# sgnd_rings.net
KiCad netlist of a schematic drawn in Altium Designer
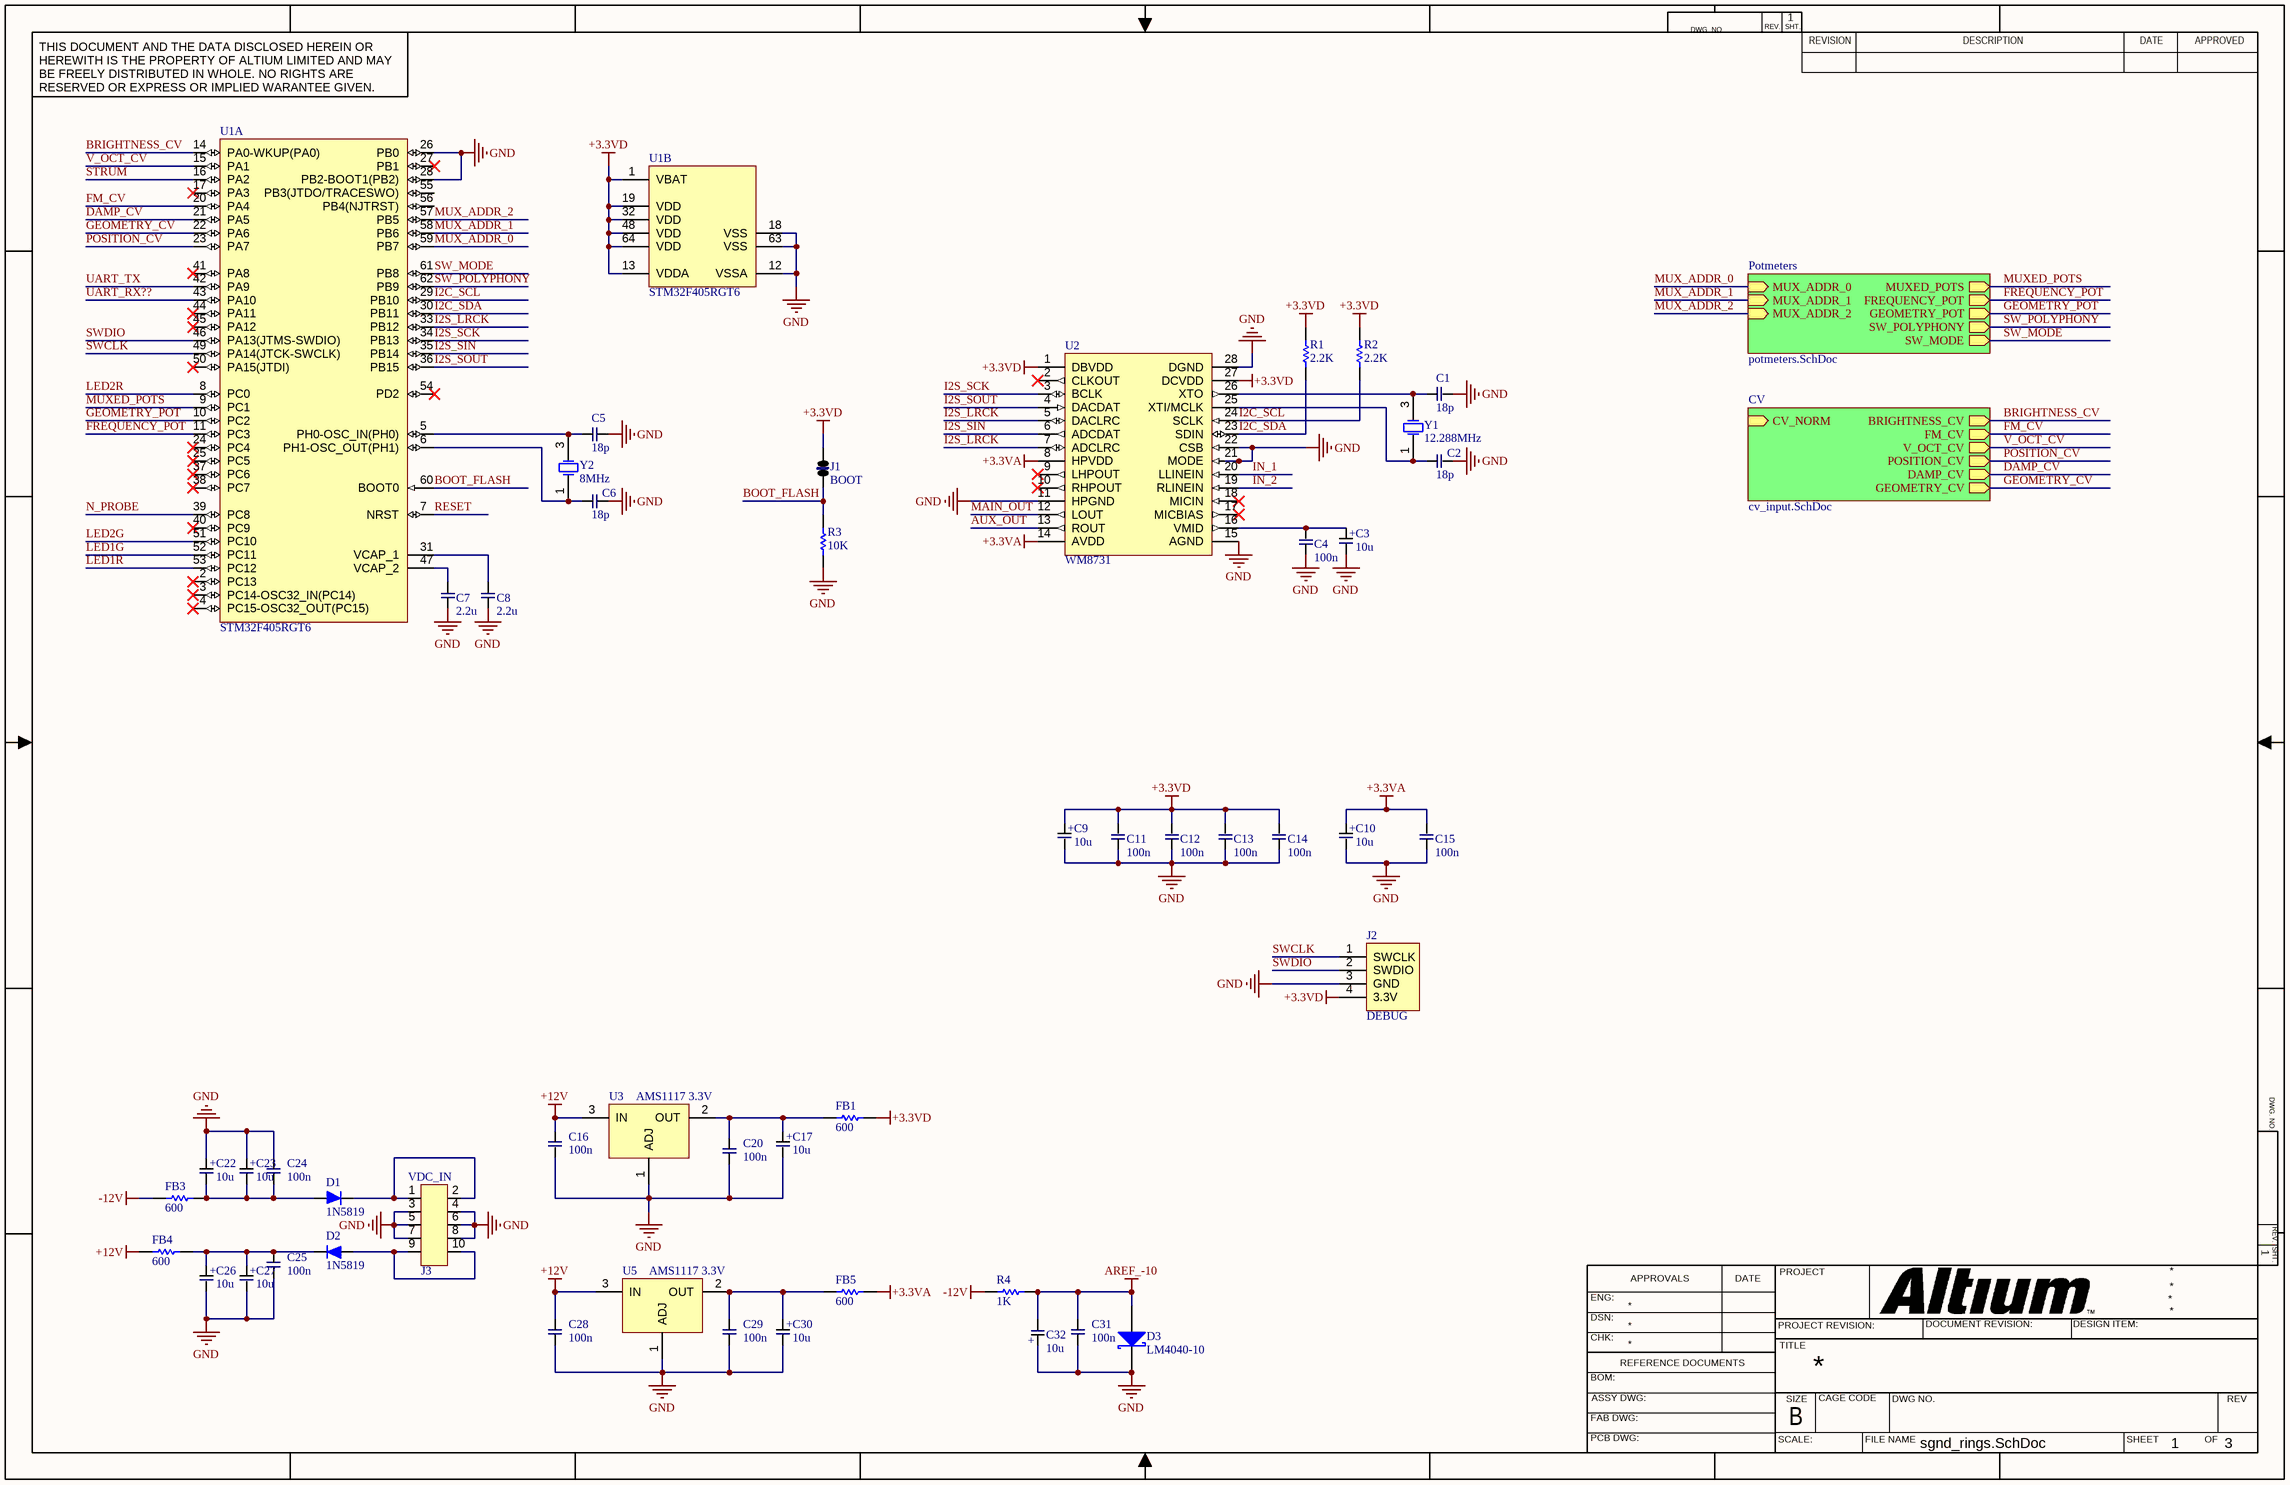
[diagram p0: sgnd_rings.SchDoc]

(export (version "E")
  (design (tool "Eeschema 10.0.6"))
  (components
    (comp (ref "C1")
      (value "18p")
      (footprint "C0603")
      (description "Capacitor (Semiconductor SIM Model)")
      (fields (field (name "Comment") "Capacitor") (field (name "PUBLISHER") "Altium Limited"))
      (libsource (lib "ryzerd") (part "Capacitor"))
    )
    (comp (ref "C2")
      (value "18p")
      (footprint "C0603")
      (description "Capacitor (Semiconductor SIM Model)")
      (fields (field (name "Comment") "Capacitor") (field (name "PUBLISHER") "Altium Limited"))
      (libsource (lib "ryzerd") (part "Capacitor"))
    )
    (comp (ref "C3")
      (value "10u")
      (footprint "ELCO_SMD_4x5.3mm")
      (fields (field (name "Comment") "C_ELCO"))
      (libsource (lib "ryzerd") (part "C_ELCO"))
    )
    (comp (ref "C4")
      (value "100n")
      (footprint "C0603")
      (description "Capacitor (Semiconductor SIM Model)")
      (fields (field (name "Comment") "Capacitor") (field (name "PUBLISHER") "Altium Limited"))
      (libsource (lib "ryzerd") (part "Capacitor"))
    )
    (comp (ref "C5")
      (value "18p")
      (footprint "C0603")
      (description "Capacitor (Semiconductor SIM Model)")
      (fields (field (name "Comment") "Capacitor") (field (name "PUBLISHER") "Altium Limited"))
      (libsource (lib "ryzerd") (part "Capacitor"))
    )
    (comp (ref "C6")
      (value "18p")
      (footprint "C0603")
      (description "Capacitor (Semiconductor SIM Model)")
      (fields (field (name "Comment") "Capacitor") (field (name "PUBLISHER") "Altium Limited"))
      (libsource (lib "ryzerd") (part "Capacitor"))
    )
    (comp (ref "C7")
      (value "2.2u")
      (footprint "C0603")
      (description "Capacitor (Semiconductor SIM Model)")
      (fields (field (name "Comment") "Capacitor") (field (name "PUBLISHER") "Altium Limited"))
      (libsource (lib "ryzerd") (part "Capacitor"))
    )
    (comp (ref "C8")
      (value "2.2u")
      (footprint "C0603")
      (description "Capacitor (Semiconductor SIM Model)")
      (fields (field (name "Comment") "Capacitor") (field (name "PUBLISHER") "Altium Limited"))
      (libsource (lib "ryzerd") (part "Capacitor"))
    )
    (comp (ref "C9")
      (value "10u")
      (footprint "ELCO_SMD_4x5.3mm")
      (fields (field (name "Comment") "C_ELCO"))
      (libsource (lib "ryzerd") (part "C_ELCO"))
    )
    (comp (ref "C10")
      (value "10u")
      (footprint "ELCO_SMD_4x5.3mm")
      (fields (field (name "Comment") "C_ELCO"))
      (libsource (lib "ryzerd") (part "C_ELCO"))
    )
    (comp (ref "C11")
      (value "100n")
      (footprint "C0603")
      (description "Capacitor (Semiconductor SIM Model)")
      (fields (field (name "Comment") "Capacitor") (field (name "PUBLISHER") "Altium Limited"))
      (libsource (lib "ryzerd") (part "Capacitor"))
    )
    (comp (ref "C12")
      (value "100n")
      (footprint "C0603")
      (description "Capacitor (Semiconductor SIM Model)")
      (fields (field (name "Comment") "Capacitor") (field (name "PUBLISHER") "Altium Limited"))
      (libsource (lib "ryzerd") (part "Capacitor"))
    )
    (comp (ref "C13")
      (value "100n")
      (footprint "C0603")
      (description "Capacitor (Semiconductor SIM Model)")
      (fields (field (name "Comment") "Capacitor") (field (name "PUBLISHER") "Altium Limited"))
      (libsource (lib "ryzerd") (part "Capacitor"))
    )
    (comp (ref "C14")
      (value "100n")
      (footprint "C0603")
      (description "Capacitor (Semiconductor SIM Model)")
      (fields (field (name "Comment") "Capacitor") (field (name "PUBLISHER") "Altium Limited"))
      (libsource (lib "ryzerd") (part "Capacitor"))
    )
    (comp (ref "C15")
      (value "100n")
      (footprint "C0603")
      (description "Capacitor (Semiconductor SIM Model)")
      (fields (field (name "Comment") "Capacitor") (field (name "PUBLISHER") "Altium Limited"))
      (libsource (lib "ryzerd") (part "Capacitor"))
    )
    (comp (ref "C16")
      (value "100n")
      (footprint "C0603")
      (description "Capacitor (Semiconductor SIM Model)")
      (fields (field (name "Comment") "Capacitor") (field (name "PUBLISHER") "Altium Limited"))
      (libsource (lib "ryzerd") (part "Capacitor"))
    )
    (comp (ref "C17")
      (value "10u")
      (footprint "ELCO_SMD_4x5.3mm")
      (fields (field (name "Comment") "C_ELCO"))
      (libsource (lib "ryzerd") (part "C_ELCO"))
    )
    (comp (ref "C20")
      (value "100n")
      (footprint "C0603")
      (description "Capacitor (Semiconductor SIM Model)")
      (fields (field (name "Comment") "Capacitor") (field (name "PUBLISHER") "Altium Limited"))
      (libsource (lib "ryzerd") (part "Capacitor"))
    )
    (comp (ref "C22")
      (value "10u")
      (footprint "ELCO_SMD_4x5.3mm")
      (fields (field (name "Comment") "C_ELCO"))
      (libsource (lib "ryzerd") (part "C_ELCO"))
    )
    (comp (ref "C23")
      (value "10u")
      (footprint "ELCO_SMD_4x5.3mm")
      (fields (field (name "Comment") "C_ELCO"))
      (libsource (lib "ryzerd") (part "C_ELCO"))
    )
    (comp (ref "C24")
      (value "100n")
      (footprint "C0603")
      (description "Capacitor (Semiconductor SIM Model)")
      (fields (field (name "Comment") "Capacitor") (field (name "PUBLISHER") "Altium Limited"))
      (libsource (lib "ryzerd") (part "Capacitor"))
    )
    (comp (ref "C25")
      (value "100n")
      (footprint "C0603")
      (description "Capacitor (Semiconductor SIM Model)")
      (fields (field (name "Comment") "Capacitor") (field (name "PUBLISHER") "Altium Limited"))
      (libsource (lib "ryzerd") (part "Capacitor"))
    )
    (comp (ref "C26")
      (value "10u")
      (footprint "ELCO_SMD_4x5.3mm")
      (fields (field (name "Comment") "C_ELCO"))
      (libsource (lib "ryzerd") (part "C_ELCO"))
    )
    (comp (ref "C27")
      (value "10u")
      (footprint "ELCO_SMD_4x5.3mm")
      (fields (field (name "Comment") "C_ELCO"))
      (libsource (lib "ryzerd") (part "C_ELCO"))
    )
    (comp (ref "C28")
      (value "100n")
      (footprint "C0603")
      (description "Capacitor (Semiconductor SIM Model)")
      (fields (field (name "Comment") "Capacitor") (field (name "PUBLISHER") "Altium Limited"))
      (libsource (lib "ryzerd") (part "Capacitor"))
    )
    (comp (ref "C29")
      (value "100n")
      (footprint "C0603")
      (description "Capacitor (Semiconductor SIM Model)")
      (fields (field (name "Comment") "Capacitor") (field (name "PUBLISHER") "Altium Limited"))
      (libsource (lib "ryzerd") (part "Capacitor"))
    )
    (comp (ref "C30")
      (value "10u")
      (footprint "ELCO_SMD_4x5.3mm")
      (fields (field (name "Comment") "C_ELCO"))
      (libsource (lib "ryzerd") (part "C_ELCO"))
    )
    (comp (ref "C31")
      (value "100n")
      (footprint "C0603")
      (description "Capacitor (Semiconductor SIM Model)")
      (fields (field (name "Comment") "Capacitor") (field (name "PUBLISHER") "Altium Limited"))
      (libsource (lib "ryzerd") (part "Capacitor"))
    )
    (comp (ref "C32")
      (value "10u")
      (footprint "ELCO_SMD_4x5.3mm")
      (fields (field (name "Comment") "C_ELCO"))
      (libsource (lib "ryzerd") (part "C_ELCO"))
    )
    (comp (ref "D1")
      (value "1N5819")
      (footprint "DIODE_SOD-123")
      (description "1 Amp General Purpose Rectifier")
      (fields (field (name "Comment") "1N4148") (field (name "PUBLISHER") "Altium Limited"))
      (libsource (lib "ryzerd") (part "1N5819"))
    )
    (comp (ref "D2")
      (value "1N5819")
      (footprint "DIODE_SOD-123")
      (description "1 Amp General Purpose Rectifier")
      (fields (field (name "Comment") "1N4148") (field (name "PUBLISHER") "Altium Limited"))
      (libsource (lib "ryzerd") (part "1N5819"))
    )
    (comp (ref "D3")
      (value "LM4040-10")
      (footprint "SOT-23_M")
      (description "LM4040 Precision Micropower Shunt Voltage Reference 10V")
      (fields (field (name "JLC PART NUMBER") "C201738"))
      (libsource (lib "ryzerd") (part "LM4040-10"))
    )
    (comp (ref "FB1")
      (value "600")
      (footprint "R0603")
      (description "Resistor")
      (fields (field (name "Comment") "RESISTOR") (field (name "PUBLISHER") "Altium Limited"))
      (libsource (lib "ryzerd") (part "RESISTOR"))
    )
    (comp (ref "FB3")
      (value "600")
      (footprint "R0603")
      (description "Resistor")
      (fields (field (name "Comment") "RESISTOR") (field (name "PUBLISHER") "Altium Limited"))
      (libsource (lib "ryzerd") (part "RESISTOR"))
    )
    (comp (ref "FB4")
      (value "600")
      (footprint "R0603")
      (description "Resistor")
      (fields (field (name "Comment") "RESISTOR") (field (name "PUBLISHER") "Altium Limited"))
      (libsource (lib "ryzerd") (part "RESISTOR"))
    )
    (comp (ref "FB5")
      (value "600")
      (footprint "R0603")
      (description "Resistor")
      (fields (field (name "Comment") "RESISTOR") (field (name "PUBLISHER") "Altium Limited"))
      (libsource (lib "ryzerd") (part "RESISTOR"))
    )
    (comp (ref "J1")
      (value "BOOT")
      (footprint "JUMPER_2.54")
      (description "Jumper Wire")
      (fields (field (name "PUBLISHER") "Altium Limited"))
      (libsource (lib "ryzerd") (part "Jumper"))
    )
    (comp (ref "J2")
      (value "DEBUG")
      (footprint "4PIN_CONNECTOR_VERTICAL_1,25MM_P - duplicate")
      (libsource (lib "ryzerd") (part "STM32_SWD_PROGRAMMER"))
    )
    (comp (ref "J3")
      (value "IDC_socket_10pin")
      (footprint "IDC10")
      (libsource (lib "part_library_by.Craft") (part "IDC_socket_10pin"))
    )
    (comp (ref "R1")
      (value "2.2K")
      (footprint "R0603")
      (description "Resistor")
      (fields (field (name "Comment") "RESISTOR") (field (name "PUBLISHER") "Altium Limited"))
      (libsource (lib "ryzerd") (part "RESISTOR"))
    )
    (comp (ref "R2")
      (value "2.2K")
      (footprint "R0603")
      (description "Resistor")
      (fields (field (name "Comment") "RESISTOR") (field (name "PUBLISHER") "Altium Limited"))
      (libsource (lib "ryzerd") (part "RESISTOR"))
    )
    (comp (ref "R3")
      (value "10K")
      (footprint "R0603")
      (description "Resistor")
      (fields (field (name "Comment") "RESISTOR") (field (name "PUBLISHER") "Altium Limited"))
      (libsource (lib "ryzerd") (part "RESISTOR"))
    )
    (comp (ref "R4")
      (value "1K")
      (footprint "R0603")
      (description "Resistor")
      (fields (field (name "Comment") "RESISTOR") (field (name "PUBLISHER") "Altium Limited"))
      (libsource (lib "ryzerd") (part "RESISTOR"))
    )
    (comp (ref "U1")
      (value "STM32F405RGT6")
      (footprint "STM-LQFP64_N")
      (fields (field (name "MANUFACTURER") "STMicroelectronics"))
      (libsource (lib "ryzerd") (part "STM32F405RGT6"))
    )
    (comp (ref "U2")
      (value "WM8731")
      (footprint "SSOP-28_L")
      (description "Portable Internet Audio CODEC with Headphone Driver\r\nand Programmable Sample Rates")
      (fields (field (name "MANUFACTURER") "Microchip") (field (name "PARTNUMBER") "MCP4822-E/P"))
      (libsource (lib "ryzerd") (part "WM8731"))
    )
    (comp (ref "U3")
      (value "AMS1117 3.3V")
      (footprint "SOT223")
      (fields (field (name "Comment") "AMS1117_5V"))
      (libsource (lib "ryzerd") (part "AMS1117_5V"))
    )
    (comp (ref "U5")
      (value "AMS1117 3.3V")
      (footprint "SOT223")
      (fields (field (name "Comment") "AMS1117_5V"))
      (libsource (lib "ryzerd") (part "AMS1117_5V"))
    )
    (comp (ref "Y1")
      (value "12.288MHz")
      (footprint "XTAL_SMD_3.2x2.5x0.8")
      (description "Crystal Oscillator")
      (fields (field (name "PUBLISHER") "Altium Limited"))
      (libsource (lib "ryzerd") (part "XTAL_3225-24.576M-SR"))
    )
    (comp (ref "Y2")
      (value "8MHz")
      (footprint "XTAL_SMD_3.2x2.5x0.8")
      (description "Crystal Oscillator")
      (fields (field (name "PUBLISHER") "Altium Limited"))
      (libsource (lib "ryzerd") (part "XTAL_3225-24.576M-SR"))
    )
  )
  (nets
    (net (code "1") (name "+3.3VA") (class "Default")
      (node (ref "C10") (pin "1") (pinfunction "+_1") (pintype "passive"))
      (node (ref "C15") (pin "2") (pinfunction "2_2") (pintype "passive"))
      (node (ref "FB5") (pin "1") (pinfunction "1_1") (pintype "passive"))
      (node (ref "U2") (pin "14") (pinfunction "AVDD_14") (pintype "power_in"))
      (node (ref "U2") (pin "8") (pinfunction "HPVDD_8") (pintype "power_in"))
    )
    (net (code "2") (name "+3.3VD") (class "Default")
      (node (ref "C11") (pin "2") (pinfunction "2_2") (pintype "passive"))
      (node (ref "C12") (pin "2") (pinfunction "2_2") (pintype "passive"))
      (node (ref "C13") (pin "2") (pinfunction "2_2") (pintype "passive"))
      (node (ref "C14") (pin "2") (pinfunction "2_2") (pintype "passive"))
      (node (ref "C9") (pin "1") (pinfunction "+_1") (pintype "passive"))
      (node (ref "FB1") (pin "1") (pinfunction "1_1") (pintype "passive"))
      (node (ref "J1") (pin "2") (pinfunction "C2_2") (pintype "passive"))
      (node (ref "J2") (pin "4") (pinfunction "3.3V_4") (pintype "passive"))
      (node (ref "R1") (pin "2") (pinfunction "2_2") (pintype "passive"))
      (node (ref "R2") (pin "2") (pinfunction "2_2") (pintype "passive"))
      (node (ref "U1") (pin "1") (pinfunction "VBAT_1") (pintype "power_in"))
      (node (ref "U1") (pin "13") (pinfunction "VDDA_13") (pintype "power_in"))
      (node (ref "U1") (pin "19") (pinfunction "VDD_19") (pintype "power_in"))
      (node (ref "U1") (pin "32") (pinfunction "VDD_32") (pintype "power_in"))
      (node (ref "U1") (pin "48") (pinfunction "VDD_48") (pintype "power_in"))
      (node (ref "U1") (pin "64") (pinfunction "VDD_64") (pintype "power_in"))
      (node (ref "U2") (pin "1") (pinfunction "DBVDD_1") (pintype "power_in"))
      (node (ref "U2") (pin "27") (pinfunction "DCVDD_27") (pintype "power_in"))
    )
    (net (code "3") (name "+12V") (class "Default")
      (node (ref "C16") (pin "1") (pinfunction "1_1") (pintype "passive"))
      (node (ref "C28") (pin "1") (pinfunction "1_1") (pintype "passive"))
      (node (ref "FB4") (pin "2") (pinfunction "2_2") (pintype "passive"))
      (node (ref "U3") (pin "3") (pinfunction "IN_3") (pintype "passive"))
      (node (ref "U5") (pin "3") (pinfunction "IN_3") (pintype "passive"))
    )
    (net (code "4") (name "-12V") (class "Default")
      (node (ref "FB3") (pin "2") (pinfunction "2_2") (pintype "passive"))
      (node (ref "R4") (pin "2") (pinfunction "2_2") (pintype "passive"))
    )
    (net (code "5") (name "/AUX_OUT") (class "Default")
      (node (ref "U2") (pin "13") (pinfunction "ROUT_13") (pintype "output"))
    )
    (net (code "6") (name "/BOOT_FLASH") (class "Default")
      (node (ref "J1") (pin "1") (pinfunction "C1_1") (pintype "passive"))
      (node (ref "R3") (pin "2") (pinfunction "2_2") (pintype "passive"))
      (node (ref "U1") (pin "60") (pinfunction "BOOT0_60") (pintype "input"))
    )
    (net (code "7") (name "/BRIGHTNESS_CV") (class "Default")
      (node (ref "U1") (pin "14") (pinfunction "PA0-WKUP(PA0)_14") (pintype "bidirectional"))
    )
    (net (code "9") (name "/DAMP_CV") (class "Default")
      (node (ref "U1") (pin "21") (pinfunction "PA5_21") (pintype "bidirectional"))
    )
    (net (code "10") (name "/FM_CV") (class "Default")
      (node (ref "U1") (pin "20") (pinfunction "PA4_20") (pintype "bidirectional"))
    )
    (net (code "11") (name "/FREQUENCY_POT") (class "Default")
      (node (ref "U1") (pin "11") (pinfunction "PC3_11") (pintype "bidirectional"))
    )
    (net (code "12") (name "/GEOMETRY_CV") (class "Default")
      (node (ref "U1") (pin "22") (pinfunction "PA6_22") (pintype "bidirectional"))
    )
    (net (code "13") (name "/GEOMETRY_POT") (class "Default")
      (node (ref "U1") (pin "10") (pinfunction "PC2_10") (pintype "bidirectional"))
    )
    (net (code "14") (name "/I2C_SCL") (class "Default")
      (node (ref "R2") (pin "1") (pinfunction "1_1") (pintype "passive"))
      (node (ref "U1") (pin "29") (pinfunction "PB10_29") (pintype "bidirectional"))
      (node (ref "U2") (pin "24") (pinfunction "SCLK_24") (pintype "input"))
    )
    (net (code "15") (name "/I2C_SDA") (class "Default")
      (node (ref "R1") (pin "1") (pinfunction "1_1") (pintype "passive"))
      (node (ref "U1") (pin "30") (pinfunction "PB11_30") (pintype "bidirectional"))
      (node (ref "U2") (pin "23") (pinfunction "SDIN_23") (pintype "bidirectional"))
    )
    (net (code "16") (name "/I2S_LRCK") (class "Default")
      (node (ref "U1") (pin "33") (pinfunction "PB12_33") (pintype "bidirectional"))
      (node (ref "U2") (pin "5") (pinfunction "DACLRC_5") (pintype "bidirectional"))
      (node (ref "U2") (pin "7") (pinfunction "ADCLRC_7") (pintype "bidirectional"))
    )
    (net (code "17") (name "/I2S_SCK") (class "Default")
      (node (ref "U1") (pin "34") (pinfunction "PB13_34") (pintype "bidirectional"))
      (node (ref "U2") (pin "3") (pinfunction "BCLK_3") (pintype "bidirectional"))
    )
    (net (code "18") (name "/I2S_SIN") (class "Default")
      (node (ref "U1") (pin "35") (pinfunction "PB14_35") (pintype "bidirectional"))
      (node (ref "U2") (pin "6") (pinfunction "ADCDAT_6") (pintype "output"))
    )
    (net (code "19") (name "/I2S_SOUT") (class "Default")
      (node (ref "U1") (pin "36") (pinfunction "PB15_36") (pintype "bidirectional"))
      (node (ref "U2") (pin "4") (pinfunction "DACDAT_4") (pintype "input"))
    )
    (net (code "20") (name "/IN_1") (class "Default")
      (node (ref "U2") (pin "20") (pinfunction "LLINEIN_20") (pintype "input"))
    )
    (net (code "21") (name "/IN_2") (class "Default")
      (node (ref "U2") (pin "19") (pinfunction "RLINEIN_19") (pintype "input"))
    )
    (net (code "22") (name "/LED1G") (class "Default")
      (node (ref "U1") (pin "52") (pinfunction "PC11_52") (pintype "bidirectional"))
    )
    (net (code "23") (name "/LED1R") (class "Default")
      (node (ref "U1") (pin "53") (pinfunction "PC12_53") (pintype "bidirectional"))
    )
    (net (code "24") (name "/LED2G") (class "Default")
      (node (ref "U1") (pin "51") (pinfunction "PC10_51") (pintype "bidirectional"))
    )
    (net (code "25") (name "/LED2R") (class "Default")
      (node (ref "U1") (pin "8") (pinfunction "PC0_8") (pintype "bidirectional"))
    )
    (net (code "26") (name "/MAIN_OUT") (class "Default")
      (node (ref "U2") (pin "12") (pinfunction "LOUT_12") (pintype "output"))
    )
    (net (code "27") (name "/MUXED_POTS") (class "Default")
      (node (ref "U1") (pin "9") (pinfunction "PC1_9") (pintype "bidirectional"))
    )
    (net (code "28") (name "/MUX_ADDR_0") (class "Default")
      (node (ref "U1") (pin "59") (pinfunction "PB7_59") (pintype "bidirectional"))
    )
    (net (code "29") (name "/MUX_ADDR_1") (class "Default")
      (node (ref "U1") (pin "58") (pinfunction "PB6_58") (pintype "bidirectional"))
    )
    (net (code "30") (name "/MUX_ADDR_2") (class "Default")
      (node (ref "U1") (pin "57") (pinfunction "PB5_57") (pintype "bidirectional"))
    )
    (net (code "31") (name "/N_PROBE") (class "Default")
      (node (ref "U1") (pin "39") (pinfunction "PC8_39") (pintype "bidirectional"))
    )
    (net (code "32") (name "/POSITION_CV") (class "Default")
      (node (ref "U1") (pin "23") (pinfunction "PA7_23") (pintype "bidirectional"))
    )
    (net (code "33") (name "/RESET") (class "Default")
      (node (ref "U1") (pin "7") (pinfunction "NRST_7") (pintype "bidirectional"))
    )
    (net (code "34") (name "/STRUM") (class "Default")
      (node (ref "U1") (pin "16") (pinfunction "PA2_16") (pintype "bidirectional"))
    )
    (net (code "35") (name "/SWCLK") (class "Default")
      (node (ref "J2") (pin "1") (pinfunction "SWCLK_1") (pintype "passive"))
      (node (ref "U1") (pin "49") (pinfunction "PA14(JTCK-SWCLK)_49") (pintype "bidirectional"))
    )
    (net (code "36") (name "/SWDIO") (class "Default")
      (node (ref "J2") (pin "2") (pinfunction "SWDIO_2") (pintype "passive"))
      (node (ref "U1") (pin "46") (pinfunction "PA13(JTMS-SWDIO)_46") (pintype "bidirectional"))
    )
    (net (code "37") (name "/SW_MODE") (class "Default")
      (node (ref "U1") (pin "61") (pinfunction "PB8_61") (pintype "bidirectional"))
    )
    (net (code "38") (name "/SW_POLYPHONY") (class "Default")
      (node (ref "U1") (pin "62") (pinfunction "PB9_62") (pintype "bidirectional"))
    )
    (net (code "39") (name "/UART_RX??") (class "Default")
      (node (ref "U1") (pin "43") (pinfunction "PA10_43") (pintype "bidirectional"))
    )
    (net (code "40") (name "/UART_TX") (class "Default")
      (node (ref "U1") (pin "42") (pinfunction "PA9_42") (pintype "bidirectional"))
    )
    (net (code "41") (name "/V_OCT_CV") (class "Default")
      (node (ref "U1") (pin "15") (pinfunction "PA1_15") (pintype "bidirectional"))
    )
    (net (code "42") (name "AREF_-10") (class "Default")
      (node (ref "C31") (pin "1") (pinfunction "1_1") (pintype "passive"))
      (node (ref "C32") (pin "2") (pinfunction "-_2") (pintype "passive"))
      (node (ref "D3") (pin "2") (pinfunction "-_2") (pintype "passive"))
      (node (ref "R4") (pin "1") (pinfunction "1_1") (pintype "passive"))
    )
    (net (code "43") (name "GND") (class "Default")
      (node (ref "C1") (pin "2") (pinfunction "2_2") (pintype "passive"))
      (node (ref "C10") (pin "2") (pinfunction "-_2") (pintype "passive"))
      (node (ref "C11") (pin "1") (pinfunction "1_1") (pintype "passive"))
      (node (ref "C12") (pin "1") (pinfunction "1_1") (pintype "passive"))
      (node (ref "C13") (pin "1") (pinfunction "1_1") (pintype "passive"))
      (node (ref "C14") (pin "1") (pinfunction "1_1") (pintype "passive"))
      (node (ref "C15") (pin "1") (pinfunction "1_1") (pintype "passive"))
      (node (ref "C16") (pin "2") (pinfunction "2_2") (pintype "passive"))
      (node (ref "C17") (pin "2") (pinfunction "-_2") (pintype "passive"))
      (node (ref "C2") (pin "2") (pinfunction "2_2") (pintype "passive"))
      (node (ref "C20") (pin "2") (pinfunction "2_2") (pintype "passive"))
      (node (ref "C22") (pin "1") (pinfunction "+_1") (pintype "passive"))
      (node (ref "C23") (pin "1") (pinfunction "+_1") (pintype "passive"))
      (node (ref "C24") (pin "1") (pinfunction "1_1") (pintype "passive"))
      (node (ref "C25") (pin "2") (pinfunction "2_2") (pintype "passive"))
      (node (ref "C26") (pin "2") (pinfunction "-_2") (pintype "passive"))
      (node (ref "C27") (pin "2") (pinfunction "-_2") (pintype "passive"))
      (node (ref "C28") (pin "2") (pinfunction "2_2") (pintype "passive"))
      (node (ref "C29") (pin "2") (pinfunction "2_2") (pintype "passive"))
      (node (ref "C3") (pin "2") (pinfunction "-_2") (pintype "passive"))
      (node (ref "C30") (pin "2") (pinfunction "-_2") (pintype "passive"))
      (node (ref "C31") (pin "2") (pinfunction "2_2") (pintype "passive"))
      (node (ref "C32") (pin "1") (pinfunction "+_1") (pintype "passive"))
      (node (ref "C4") (pin "1") (pinfunction "1_1") (pintype "passive"))
      (node (ref "C5") (pin "2") (pinfunction "2_2") (pintype "passive"))
      (node (ref "C6") (pin "2") (pinfunction "2_2") (pintype "passive"))
      (node (ref "C7") (pin "1") (pinfunction "1_1") (pintype "passive"))
      (node (ref "C8") (pin "1") (pinfunction "1_1") (pintype "passive"))
      (node (ref "C9") (pin "2") (pinfunction "-_2") (pintype "passive"))
      (node (ref "D3") (pin "1") (pinfunction "+_1") (pintype "passive"))
      (node (ref "J2") (pin "3") (pinfunction "GND_3") (pintype "passive"))
      (node (ref "J3") (pin "3") (pintype "passive"))
      (node (ref "J3") (pin "4") (pintype "passive"))
      (node (ref "J3") (pin "5") (pintype "passive"))
      (node (ref "J3") (pin "6") (pintype "passive"))
      (node (ref "J3") (pin "7") (pintype "passive"))
      (node (ref "J3") (pin "8") (pintype "passive"))
      (node (ref "R3") (pin "1") (pinfunction "1_1") (pintype "passive"))
      (node (ref "U1") (pin "12") (pinfunction "VSSA_12") (pintype "power_in"))
      (node (ref "U1") (pin "18") (pinfunction "VSS_18") (pintype "power_in"))
      (node (ref "U1") (pin "26") (pinfunction "PB0_26") (pintype "bidirectional"))
      (node (ref "U1") (pin "28") (pinfunction "PB2-BOOT1(PB2)_28") (pintype "bidirectional"))
      (node (ref "U1") (pin "63") (pinfunction "VSS_63") (pintype "power_in"))
      (node (ref "U2") (pin "11") (pinfunction "HPGND_11") (pintype "power_in"))
      (node (ref "U2") (pin "15") (pinfunction "AGND_15") (pintype "power_in"))
      (node (ref "U2") (pin "21") (pinfunction "MODE_21") (pintype "input"))
      (node (ref "U2") (pin "22") (pinfunction "CSB_22") (pintype "input"))
      (node (ref "U2") (pin "28") (pinfunction "DGND_28") (pintype "power_in"))
      (node (ref "U3") (pin "1") (pinfunction "ADJ_1") (pintype "passive"))
      (node (ref "U5") (pin "1") (pinfunction "ADJ_1") (pintype "passive"))
    )
    (net (code "44") (name "Net-(C3-+)") (class "Default")
      (node (ref "C3") (pin "1") (pinfunction "+_1") (pintype "passive"))
      (node (ref "C4") (pin "2") (pinfunction "2_2") (pintype "passive"))
      (node (ref "U2") (pin "16") (pinfunction "VMID_16") (pintype "output"))
    )
    (net (code "45") (name "Net-(C17-+)") (class "Default")
      (node (ref "C17") (pin "1") (pinfunction "+_1") (pintype "passive"))
      (node (ref "C20") (pin "1") (pinfunction "1_1") (pintype "passive"))
      (node (ref "FB1") (pin "2") (pinfunction "2_2") (pintype "passive"))
      (node (ref "U3") (pin "2") (pinfunction "OUT_2") (pintype "passive"))
    )
    (net (code "46") (name "Net-(C22--)") (class "Default")
      (node (ref "C22") (pin "2") (pinfunction "-_2") (pintype "passive"))
      (node (ref "C23") (pin "2") (pinfunction "-_2") (pintype "passive"))
      (node (ref "C24") (pin "2") (pinfunction "2_2") (pintype "passive"))
      (node (ref "D1") (pin "2") (pinfunction "A_2") (pintype "passive"))
      (node (ref "FB3") (pin "1") (pinfunction "1_1") (pintype "passive"))
    )
    (net (code "47") (name "Net-(C26-+)") (class "Default")
      (node (ref "C25") (pin "1") (pinfunction "1_1") (pintype "passive"))
      (node (ref "C26") (pin "1") (pinfunction "+_1") (pintype "passive"))
      (node (ref "C27") (pin "1") (pinfunction "+_1") (pintype "passive"))
      (node (ref "D2") (pin "1") (pinfunction "K_1") (pintype "passive"))
      (node (ref "FB4") (pin "1") (pinfunction "1_1") (pintype "passive"))
    )
    (net (code "48") (name "Net-(C30-+)") (class "Default")
      (node (ref "C29") (pin "1") (pinfunction "1_1") (pintype "passive"))
      (node (ref "C30") (pin "1") (pinfunction "+_1") (pintype "passive"))
      (node (ref "FB5") (pin "2") (pinfunction "2_2") (pintype "passive"))
      (node (ref "U5") (pin "2") (pinfunction "OUT_2") (pintype "passive"))
    )
    (net (code "49") (name "Net-(D1-K)") (class "Default")
      (node (ref "D1") (pin "1") (pinfunction "K_1") (pintype "passive"))
      (node (ref "J3") (pin "1") (pintype "passive"))
      (node (ref "J3") (pin "2") (pintype "passive"))
    )
    (net (code "50") (name "Net-(D2-A)") (class "Default")
      (node (ref "D2") (pin "2") (pinfunction "A_2") (pintype "passive"))
      (node (ref "J3") (pin "10") (pintype "passive"))
      (node (ref "J3") (pin "9") (pintype "passive"))
    )
    (net (code "51") (name "Net-(U1A-PH0-OSC_IN(PH0))") (class "Default")
      (node (ref "C5") (pin "1") (pinfunction "1_1") (pintype "passive"))
      (node (ref "U1") (pin "5") (pinfunction "PH0-OSC_IN(PH0)_5") (pintype "bidirectional"))
      (node (ref "Y2") (pin "3") (pinfunction "OSC2_3") (pintype "passive"))
    )
    (net (code "52") (name "Net-(U1A-PH1-OSC_OUT(PH1))") (class "Default")
      (node (ref "C6") (pin "1") (pinfunction "1_1") (pintype "passive"))
      (node (ref "U1") (pin "6") (pinfunction "PH1-OSC_OUT(PH1)_6") (pintype "bidirectional"))
      (node (ref "Y2") (pin "1") (pinfunction "OSC1_1") (pintype "passive"))
    )
    (net (code "53") (name "Net-(U1A-VCAP_1)") (class "Default")
      (node (ref "C8") (pin "2") (pinfunction "2_2") (pintype "passive"))
      (node (ref "U1") (pin "31") (pinfunction "VCAP_1_31") (pintype "power_in"))
    )
    (net (code "54") (name "Net-(U1A-VCAP_2)") (class "Default")
      (node (ref "C7") (pin "2") (pinfunction "2_2") (pintype "passive"))
      (node (ref "U1") (pin "47") (pinfunction "VCAP_2_47") (pintype "power_in"))
    )
    (net (code "55") (name "Net-(U2-XTI{slash}MCLK)") (class "Default")
      (node (ref "C2") (pin "1") (pinfunction "1_1") (pintype "passive"))
      (node (ref "U2") (pin "25") (pinfunction "XTI/MCLK_25") (pintype "power_in"))
      (node (ref "Y1") (pin "1") (pinfunction "OSC1_1") (pintype "passive"))
    )
    (net (code "56") (name "Net-(U2-XTO)") (class "Default")
      (node (ref "C1") (pin "1") (pinfunction "1_1") (pintype "passive"))
      (node (ref "U2") (pin "26") (pinfunction "XTO_26") (pintype "output"))
      (node (ref "Y1") (pin "3") (pinfunction "OSC2_3") (pintype "passive"))
    )
    (net (code "57") (name "unconnected-(U1A-PA3-Pad17)") (class "Default")
      (node (ref "U1") (pin "17") (pinfunction "PA3_17") (pintype "bidirectional+no_connect"))
    )
    (net (code "58") (name "unconnected-(U1A-PA8-Pad41)") (class "Default")
      (node (ref "U1") (pin "41") (pinfunction "PA8_41") (pintype "bidirectional+no_connect"))
    )
    (net (code "59") (name "unconnected-(U1A-PA11-Pad44)") (class "Default")
      (node (ref "U1") (pin "44") (pinfunction "PA11_44") (pintype "bidirectional+no_connect"))
    )
    (net (code "60") (name "unconnected-(U1A-PA12-Pad45)") (class "Default")
      (node (ref "U1") (pin "45") (pinfunction "PA12_45") (pintype "bidirectional+no_connect"))
    )
    (net (code "61") (name "unconnected-(U1A-PA15(JTDI)-Pad50)") (class "Default")
      (node (ref "U1") (pin "50") (pinfunction "PA15(JTDI)_50") (pintype "bidirectional+no_connect"))
    )
    (net (code "62") (name "unconnected-(U1A-PB1-Pad27)") (class "Default")
      (node (ref "U1") (pin "27") (pinfunction "PB1_27") (pintype "bidirectional+no_connect"))
    )
    (net (code "63") (name "unconnected-(U1A-PB3(JTDO{slash}TRACESWO)-Pad55)") (class "Default")
      (node (ref "U1") (pin "55") (pinfunction "PB3(JTDO/TRACESWO)_55") (pintype "bidirectional"))
    )
    (net (code "64") (name "unconnected-(U1A-PB4(NJTRST)-Pad56)") (class "Default")
      (node (ref "U1") (pin "56") (pinfunction "PB4(NJTRST)_56") (pintype "bidirectional"))
    )
    (net (code "65") (name "unconnected-(U1A-PC4-Pad24)") (class "Default")
      (node (ref "U1") (pin "24") (pinfunction "PC4_24") (pintype "bidirectional+no_connect"))
    )
    (net (code "66") (name "unconnected-(U1A-PC5-Pad25)") (class "Default")
      (node (ref "U1") (pin "25") (pinfunction "PC5_25") (pintype "bidirectional+no_connect"))
    )
    (net (code "67") (name "unconnected-(U1A-PC6-Pad37)") (class "Default")
      (node (ref "U1") (pin "37") (pinfunction "PC6_37") (pintype "bidirectional+no_connect"))
    )
    (net (code "68") (name "unconnected-(U1A-PC7-Pad38)") (class "Default")
      (node (ref "U1") (pin "38") (pinfunction "PC7_38") (pintype "bidirectional+no_connect"))
    )
    (net (code "69") (name "unconnected-(U1A-PC9-Pad40)") (class "Default")
      (node (ref "U1") (pin "40") (pinfunction "PC9_40") (pintype "bidirectional+no_connect"))
    )
    (net (code "70") (name "unconnected-(U1A-PC13-Pad2)") (class "Default")
      (node (ref "U1") (pin "2") (pinfunction "PC13_2") (pintype "bidirectional+no_connect"))
    )
    (net (code "71") (name "unconnected-(U1A-PC14-OSC32_IN(PC14)-Pad3)") (class "Default")
      (node (ref "U1") (pin "3") (pinfunction "PC14-OSC32_IN(PC14)_3") (pintype "bidirectional+no_connect"))
    )
    (net (code "72") (name "unconnected-(U1A-PC15-OSC32_OUT(PC15)-Pad4)") (class "Default")
      (node (ref "U1") (pin "4") (pinfunction "PC15-OSC32_OUT(PC15)_4") (pintype "bidirectional+no_connect"))
    )
    (net (code "73") (name "unconnected-(U1A-PD2-Pad54)") (class "Default")
      (node (ref "U1") (pin "54") (pinfunction "PD2_54") (pintype "bidirectional+no_connect"))
    )
    (net (code "74") (name "unconnected-(U2-CLKOUT-Pad2)") (class "Default")
      (node (ref "U2") (pin "2") (pinfunction "CLKOUT_2") (pintype "output+no_connect"))
    )
    (net (code "75") (name "unconnected-(U2-LHPOUT-Pad9)") (class "Default")
      (node (ref "U2") (pin "9") (pinfunction "LHPOUT_9") (pintype "output+no_connect"))
    )
    (net (code "76") (name "unconnected-(U2-MICBIAS-Pad17)") (class "Default")
      (node (ref "U2") (pin "17") (pinfunction "MICBIAS_17") (pintype "output+no_connect"))
    )
    (net (code "77") (name "unconnected-(U2-MICIN-Pad18)") (class "Default")
      (node (ref "U2") (pin "18") (pinfunction "MICIN_18") (pintype "input+no_connect"))
    )
    (net (code "78") (name "unconnected-(U2-RHPOUT-Pad10)") (class "Default")
      (node (ref "U2") (pin "10") (pinfunction "RHPOUT_10") (pintype "output+no_connect"))
    )
  )
)
